# Layer4.net
KiCad netlist of a schematic drawn in EAGLE
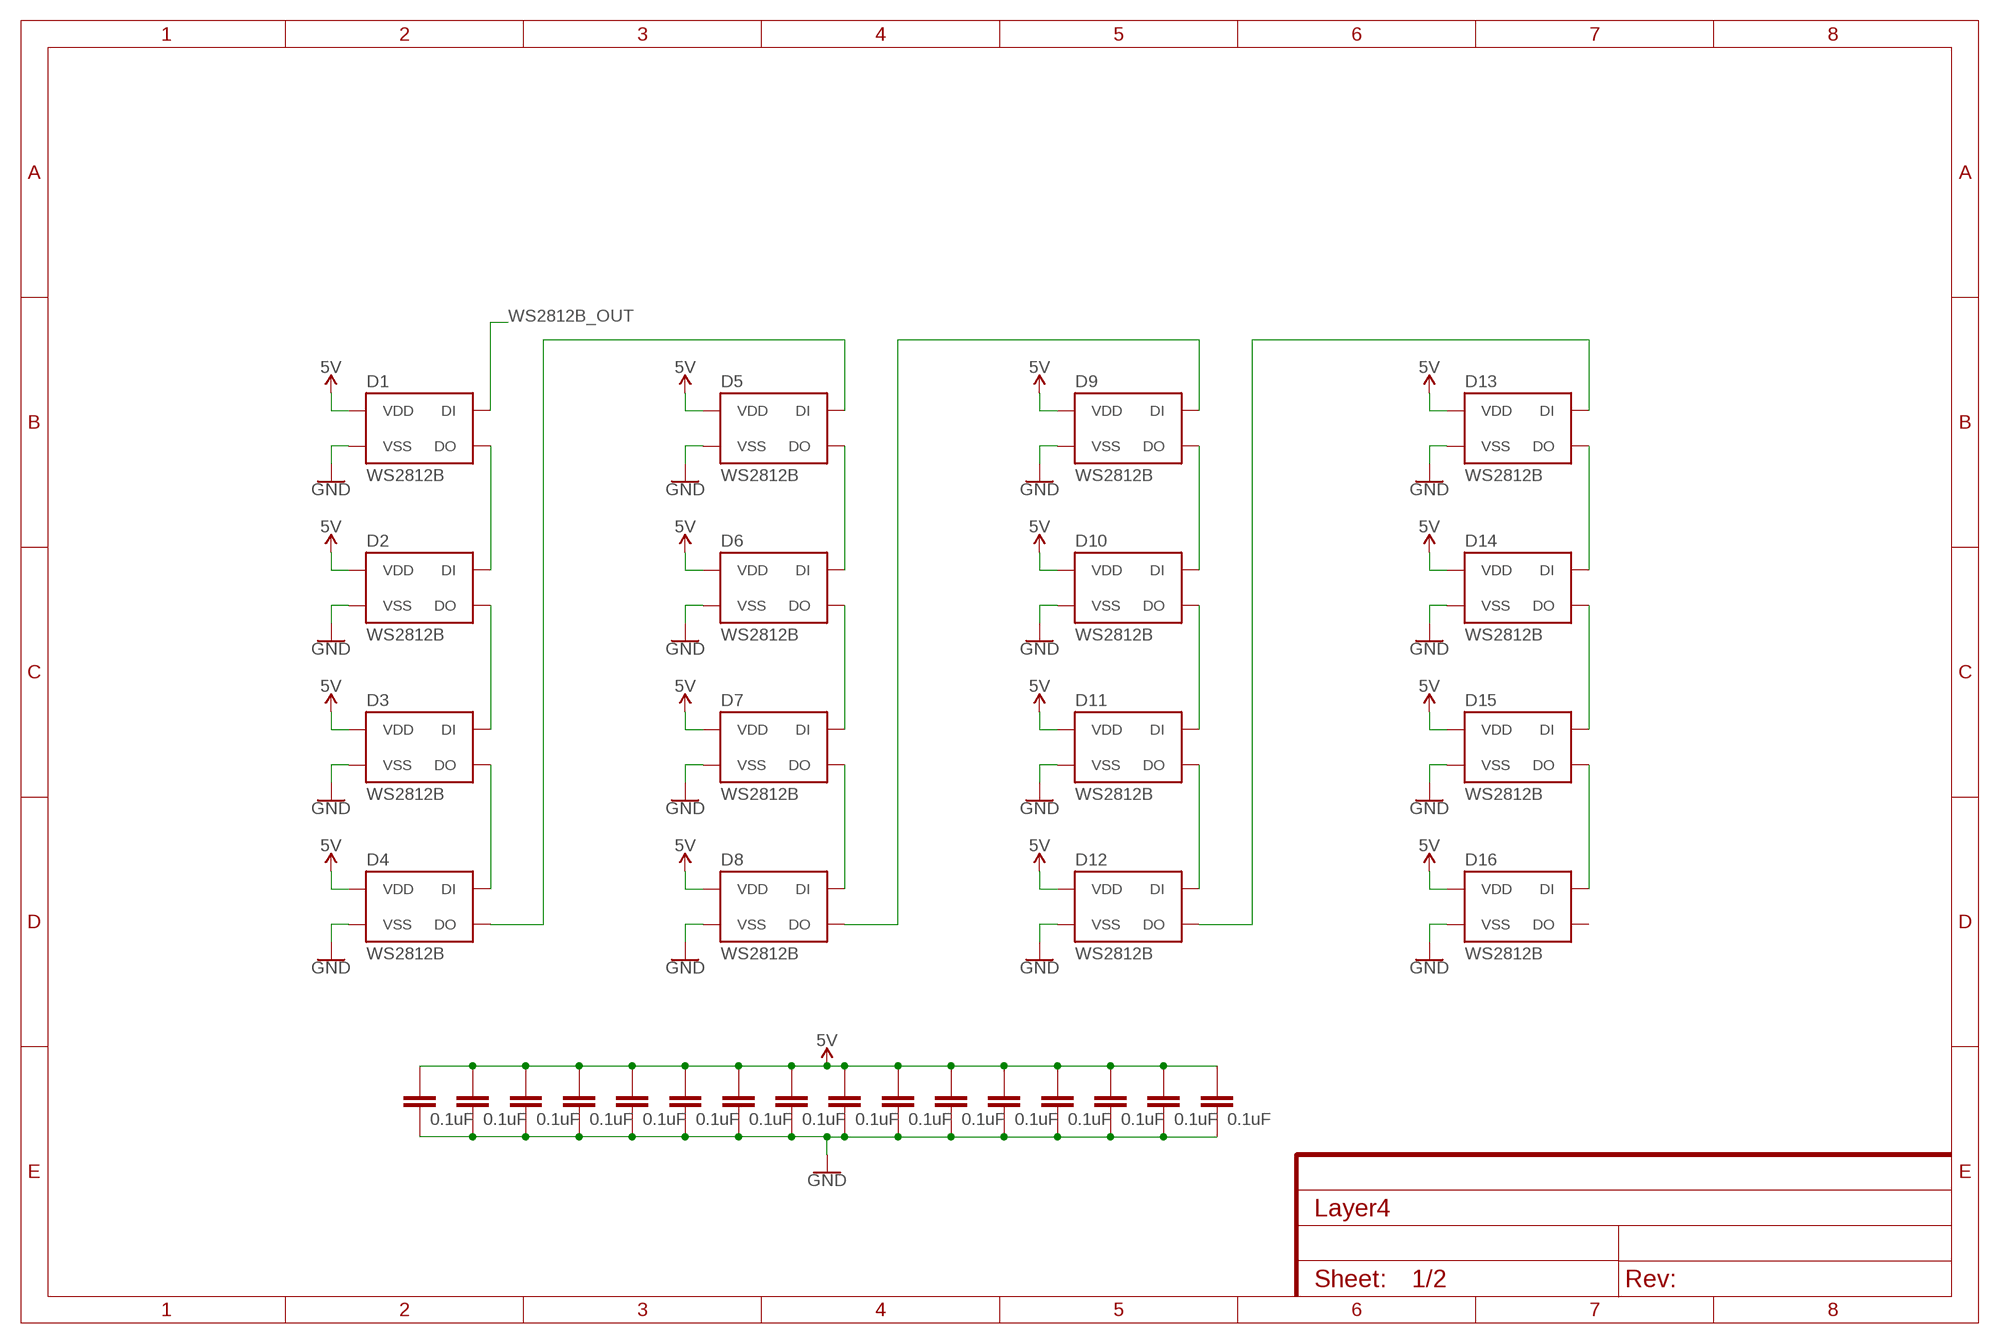
[diagram p0: schematic, sheet 1]
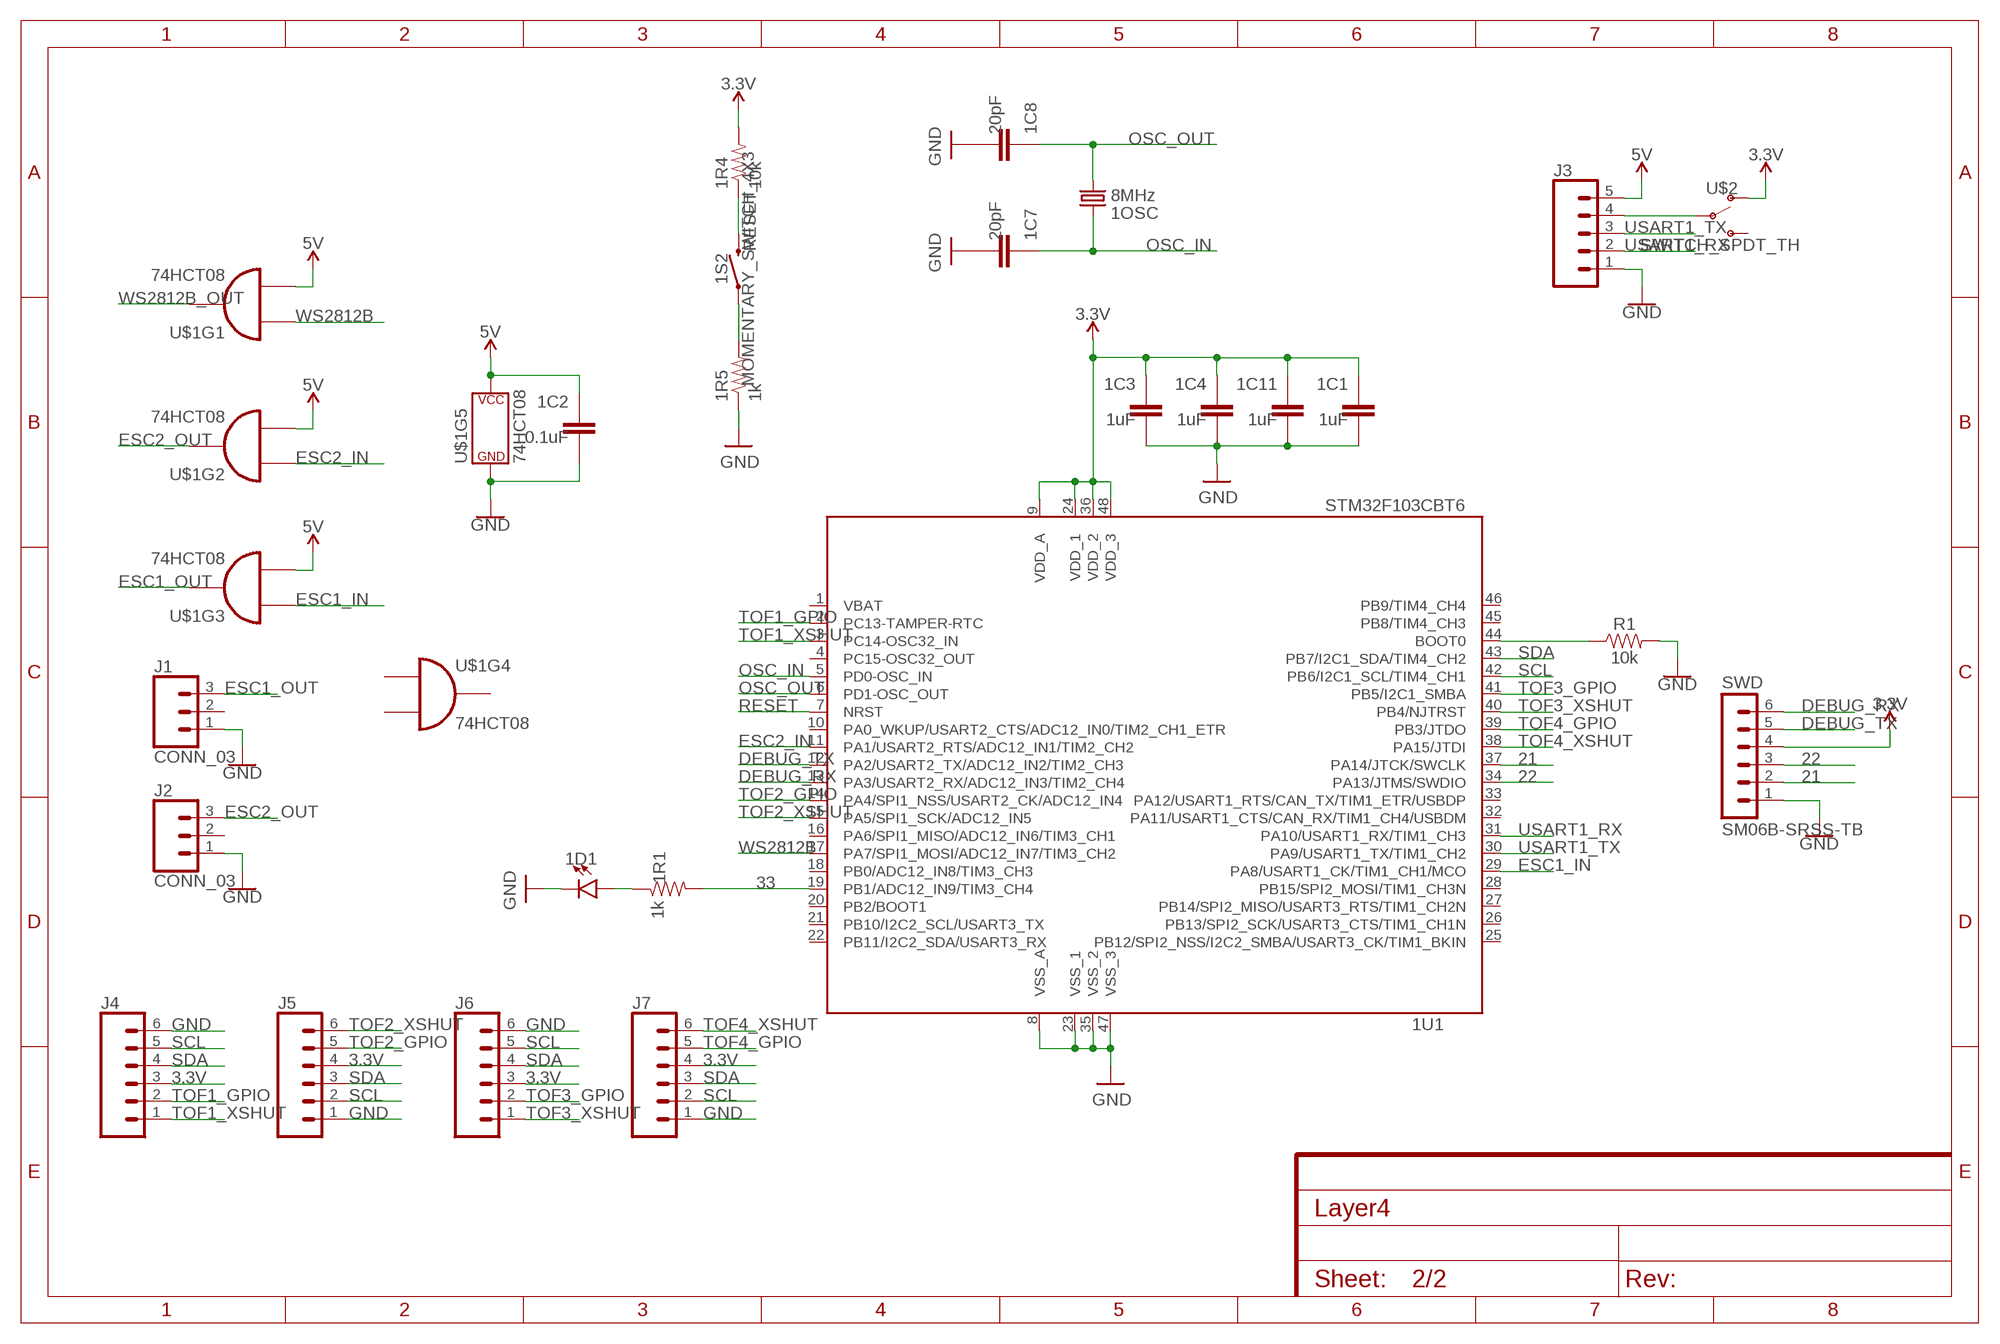
[diagram p1: schematic, sheet 2]

(export (version "E")
  (design (tool "Eeschema 10.0.6"))
  (components
    (comp (ref "AC1")
      (value "0.1uF")
      (footprint "eagle-import:C0603")
      (libsource (lib "eagle-import") (part "CAPACITOR0603"))
    )
    (comp (ref "AC2")
      (value "0.1uF")
      (footprint "eagle-import:C0603")
      (libsource (lib "eagle-import") (part "CAPACITOR0603"))
    )
    (comp (ref "AC3")
      (value "0.1uF")
      (footprint "eagle-import:C0603")
      (libsource (lib "eagle-import") (part "CAPACITOR0603"))
    )
    (comp (ref "AC4")
      (value "0.1uF")
      (footprint "eagle-import:C0603")
      (libsource (lib "eagle-import") (part "CAPACITOR0603"))
    )
    (comp (ref "AC5")
      (value "0.1uF")
      (footprint "eagle-import:C0603")
      (libsource (lib "eagle-import") (part "CAPACITOR0603"))
    )
    (comp (ref "AC6")
      (value "0.1uF")
      (footprint "eagle-import:C0603")
      (libsource (lib "eagle-import") (part "CAPACITOR0603"))
    )
    (comp (ref "AC7")
      (value "0.1uF")
      (footprint "eagle-import:C0603")
      (libsource (lib "eagle-import") (part "CAPACITOR0603"))
    )
    (comp (ref "AC8")
      (value "0.1uF")
      (footprint "eagle-import:C0603")
      (libsource (lib "eagle-import") (part "CAPACITOR0603"))
    )
    (comp (ref "C1")
      (value "0.1uF")
      (footprint "eagle-import:C0603")
      (libsource (lib "eagle-import") (part "CAPACITOR0603"))
    )
    (comp (ref "C3")
      (value "0.1uF")
      (footprint "eagle-import:C0603")
      (libsource (lib "eagle-import") (part "CAPACITOR0603"))
    )
    (comp (ref "C5")
      (value "0.1uF")
      (footprint "eagle-import:C0603")
      (libsource (lib "eagle-import") (part "CAPACITOR0603"))
    )
    (comp (ref "C7")
      (value "0.1uF")
      (footprint "eagle-import:C0603")
      (libsource (lib "eagle-import") (part "CAPACITOR0603"))
    )
    (comp (ref "C9")
      (value "0.1uF")
      (footprint "eagle-import:C0603")
      (libsource (lib "eagle-import") (part "CAPACITOR0603"))
    )
    (comp (ref "C11")
      (value "0.1uF")
      (footprint "eagle-import:C0603")
      (libsource (lib "eagle-import") (part "CAPACITOR0603"))
    )
    (comp (ref "C13")
      (value "0.1uF")
      (footprint "eagle-import:C0603")
      (libsource (lib "eagle-import") (part "CAPACITOR0603"))
    )
    (comp (ref "C15")
      (value "0.1uF")
      (footprint "eagle-import:C0603")
      (libsource (lib "eagle-import") (part "CAPACITOR0603"))
    )
    (comp (ref "D1")
      (value "WS2812B")
      (footprint "eagle-import:WS2812B")
      (libsource (lib "eagle-import") (part "WS2812B"))
    )
    (comp (ref "D2")
      (value "WS2812B")
      (footprint "eagle-import:WS2812B")
      (libsource (lib "eagle-import") (part "WS2812B"))
    )
    (comp (ref "D3")
      (value "WS2812B")
      (footprint "eagle-import:WS2812B")
      (libsource (lib "eagle-import") (part "WS2812B"))
    )
    (comp (ref "D4")
      (value "WS2812B")
      (footprint "eagle-import:WS2812B")
      (libsource (lib "eagle-import") (part "WS2812B"))
    )
    (comp (ref "D5")
      (value "WS2812B")
      (footprint "eagle-import:WS2812B")
      (libsource (lib "eagle-import") (part "WS2812B"))
    )
    (comp (ref "D6")
      (value "WS2812B")
      (footprint "eagle-import:WS2812B")
      (libsource (lib "eagle-import") (part "WS2812B"))
    )
    (comp (ref "D7")
      (value "WS2812B")
      (footprint "eagle-import:WS2812B")
      (libsource (lib "eagle-import") (part "WS2812B"))
    )
    (comp (ref "D8")
      (value "WS2812B")
      (footprint "eagle-import:WS2812B")
      (libsource (lib "eagle-import") (part "WS2812B"))
    )
    (comp (ref "D9")
      (value "WS2812B")
      (footprint "eagle-import:WS2812B")
      (libsource (lib "eagle-import") (part "WS2812B"))
    )
    (comp (ref "D10")
      (value "WS2812B")
      (footprint "eagle-import:WS2812B")
      (libsource (lib "eagle-import") (part "WS2812B"))
    )
    (comp (ref "D11")
      (value "WS2812B")
      (footprint "eagle-import:WS2812B")
      (libsource (lib "eagle-import") (part "WS2812B"))
    )
    (comp (ref "D12")
      (value "WS2812B")
      (footprint "eagle-import:WS2812B")
      (libsource (lib "eagle-import") (part "WS2812B"))
    )
    (comp (ref "D13")
      (value "WS2812B")
      (footprint "eagle-import:WS2812B")
      (libsource (lib "eagle-import") (part "WS2812B"))
    )
    (comp (ref "D14")
      (value "WS2812B")
      (footprint "eagle-import:WS2812B")
      (libsource (lib "eagle-import") (part "WS2812B"))
    )
    (comp (ref "D15")
      (value "WS2812B")
      (footprint "eagle-import:WS2812B")
      (libsource (lib "eagle-import") (part "WS2812B"))
    )
    (comp (ref "D16")
      (value "WS2812B")
      (footprint "eagle-import:WS2812B")
      (libsource (lib "eagle-import") (part "WS2812B"))
    )
    (comp (ref "1C1")
      (value "1uF")
      (footprint "eagle-import:C0603")
      (libsource (lib "eagle-import") (part "CAPACITOR0603"))
    )
    (comp (ref "1C2")
      (value "0.1uF")
      (footprint "eagle-import:C0603")
      (libsource (lib "eagle-import") (part "CAPACITOR0603"))
    )
    (comp (ref "1C3")
      (value "1uF")
      (footprint "eagle-import:C0603")
      (libsource (lib "eagle-import") (part "CAPACITOR0603"))
    )
    (comp (ref "1C4")
      (value "1uF")
      (footprint "eagle-import:C0603")
      (libsource (lib "eagle-import") (part "CAPACITOR0603"))
    )
    (comp (ref "1C7")
      (value "20pF")
      (footprint "eagle-import:C0603")
      (libsource (lib "eagle-import") (part "CAPACITOR0603"))
    )
    (comp (ref "1C8")
      (value "20pF")
      (footprint "eagle-import:C0603")
      (libsource (lib "eagle-import") (part "CAPACITOR0603"))
    )
    (comp (ref "1C11")
      (value "1uF")
      (footprint "eagle-import:C0603")
      (libsource (lib "eagle-import") (part "CAPACITOR0603"))
    )
    (comp (ref "1D1")
      (value "BLUE")
      (footprint "eagle-import:LED-0603")
      (libsource (lib "eagle-import") (part "LED0603"))
    )
    (comp (ref "1OSC")
      (value "8MHz")
      (footprint "eagle-import:CRYSTAL-SMD-5X3.2-2PAD")
      (libsource (lib "eagle-import") (part "CRYSTAL_5032"))
    )
    (comp (ref "1R1")
      (value "1k")
      (footprint "eagle-import:R0603")
      (libsource (lib "eagle-import") (part "RESISTOR0603"))
    )
    (comp (ref "1R4")
      (value "10k")
      (footprint "eagle-import:R0603")
      (libsource (lib "eagle-import") (part "RESISTOR0603"))
    )
    (comp (ref "1R5")
      (value "1k")
      (footprint "eagle-import:R0603")
      (libsource (lib "eagle-import") (part "RESISTOR0603"))
    )
    (comp (ref "1S2")
      (value "MOMENTARY_SWITCH_4X3")
      (footprint "eagle-import:MOMENTARY_SWITCH_4X3")
      (libsource (lib "eagle-import") (part "MOMENTARY_SWITCH_4X3"))
    )
    (comp (ref "1U1")
      (value "STM32F103CBT6")
      (footprint "eagle-import:LQFP48")
      (libsource (lib "eagle-import") (part "STM32F103CBT6"))
    )
    (comp (ref "J1")
      (value "CONN_03")
      (footprint "eagle-import:1X03_LOCK")
      (libsource (lib "eagle-import") (part "CONN_03"))
    )
    (comp (ref "J2")
      (value "CONN_03")
      (footprint "eagle-import:1X03_LOCK")
      (libsource (lib "eagle-import") (part "CONN_03"))
    )
    (comp (ref "J3")
      (value "CONN_05LOCK")
      (footprint "eagle-import:1X05_LOCK")
      (libsource (lib "eagle-import") (part "CONN_05LOCK"))
    )
    (comp (ref "J4")
      (value "CONN_06LOCK")
      (footprint "eagle-import:1X06_LOCK")
      (libsource (lib "eagle-import") (part "CONN_06LOCK"))
    )
    (comp (ref "J5")
      (value "CONN_06LOCK")
      (footprint "eagle-import:1X06_LOCK")
      (libsource (lib "eagle-import") (part "CONN_06LOCK"))
    )
    (comp (ref "J6")
      (value "CONN_06LOCK")
      (footprint "eagle-import:1X06_LOCK")
      (libsource (lib "eagle-import") (part "CONN_06LOCK"))
    )
    (comp (ref "J7")
      (value "CONN_06LOCK")
      (footprint "eagle-import:1X06_LOCK")
      (libsource (lib "eagle-import") (part "CONN_06LOCK"))
    )
    (comp (ref "R1")
      (value "10k")
      (footprint "eagle-import:R0603")
      (libsource (lib "eagle-import") (part "RESISTOR0603"))
    )
    (comp (ref "SWD")
      (value "SM06B-SRSS-TB")
      (footprint "eagle-import:SM06B-SRSS-TB")
      (libsource (lib "eagle-import") (part "SM06B-SRSS-TB"))
    )
    (comp (ref "U$1")
      (value "74HCT08")
      (footprint "eagle-import:SOIC-14")
      (libsource (lib "eagle-import") (part "74HCT08"))
    )
    (comp (ref "U$2")
      (value "SWITCH_SPDT_TH")
      (footprint "eagle-import:SWITCH_SPDT_PTH_11.6X4.0MM_LOCK")
      (libsource (lib "eagle-import") (part "SWITCH_SPDT_TH"))
    )
  )
  (nets
    (net (code "1") (name "3.3V") (class "Default")
      (node (ref "1C1") (pin "1") (pinfunction "1_1") (pintype "passive"))
      (node (ref "1C11") (pin "1") (pinfunction "1_1") (pintype "passive"))
      (node (ref "1C3") (pin "1") (pinfunction "1_1") (pintype "passive"))
      (node (ref "1C4") (pin "1") (pinfunction "1_1") (pintype "passive"))
      (node (ref "1R4") (pin "2") (pinfunction "2_2") (pintype "passive"))
      (node (ref "1U1") (pin "24") (pinfunction "VDD_1_24") (pintype "power_in"))
      (node (ref "1U1") (pin "36") (pinfunction "VDD_2_36") (pintype "power_in"))
      (node (ref "1U1") (pin "48") (pinfunction "VDD_3_48") (pintype "power_in"))
      (node (ref "1U1") (pin "9") (pinfunction "VDD_A_9") (pintype "power_in"))
      (node (ref "J4") (pin "3") (pinfunction "3_3") (pintype "passive"))
      (node (ref "J5") (pin "4") (pinfunction "4_4") (pintype "passive"))
      (node (ref "J6") (pin "3") (pinfunction "3_3") (pintype "passive"))
      (node (ref "J7") (pin "4") (pinfunction "4_4") (pintype "passive"))
      (node (ref "SWD") (pin "4") (pinfunction "4_4") (pintype "passive"))
      (node (ref "U$2") (pin "1") (pinfunction "O_1") (pintype "passive"))
    )
    (net (code "2") (name "5V") (class "Default")
      (node (ref "1C2") (pin "1") (pinfunction "1_1") (pintype "passive"))
      (node (ref "AC1") (pin "1") (pinfunction "1_1") (pintype "passive"))
      (node (ref "AC2") (pin "1") (pinfunction "1_1") (pintype "passive"))
      (node (ref "AC3") (pin "1") (pinfunction "1_1") (pintype "passive"))
      (node (ref "AC4") (pin "1") (pinfunction "1_1") (pintype "passive"))
      (node (ref "AC5") (pin "1") (pinfunction "1_1") (pintype "passive"))
      (node (ref "AC6") (pin "1") (pinfunction "1_1") (pintype "passive"))
      (node (ref "AC7") (pin "1") (pinfunction "1_1") (pintype "passive"))
      (node (ref "AC8") (pin "1") (pinfunction "1_1") (pintype "passive"))
      (node (ref "C1") (pin "1") (pinfunction "1_1") (pintype "passive"))
      (node (ref "C11") (pin "1") (pinfunction "1_1") (pintype "passive"))
      (node (ref "C13") (pin "1") (pinfunction "1_1") (pintype "passive"))
      (node (ref "C15") (pin "1") (pinfunction "1_1") (pintype "passive"))
      (node (ref "C3") (pin "1") (pinfunction "1_1") (pintype "passive"))
      (node (ref "C5") (pin "1") (pinfunction "1_1") (pintype "passive"))
      (node (ref "C7") (pin "1") (pinfunction "1_1") (pintype "passive"))
      (node (ref "C9") (pin "1") (pinfunction "1_1") (pintype "passive"))
      (node (ref "D1") (pin "1") (pinfunction "VDD_1") (pintype "bidirectional"))
      (node (ref "D10") (pin "1") (pinfunction "VDD_1") (pintype "bidirectional"))
      (node (ref "D11") (pin "1") (pinfunction "VDD_1") (pintype "bidirectional"))
      (node (ref "D12") (pin "1") (pinfunction "VDD_1") (pintype "bidirectional"))
      (node (ref "D13") (pin "1") (pinfunction "VDD_1") (pintype "bidirectional"))
      (node (ref "D14") (pin "1") (pinfunction "VDD_1") (pintype "bidirectional"))
      (node (ref "D15") (pin "1") (pinfunction "VDD_1") (pintype "bidirectional"))
      (node (ref "D16") (pin "1") (pinfunction "VDD_1") (pintype "bidirectional"))
      (node (ref "D2") (pin "1") (pinfunction "VDD_1") (pintype "bidirectional"))
      (node (ref "D3") (pin "1") (pinfunction "VDD_1") (pintype "bidirectional"))
      (node (ref "D4") (pin "1") (pinfunction "VDD_1") (pintype "bidirectional"))
      (node (ref "D5") (pin "1") (pinfunction "VDD_1") (pintype "bidirectional"))
      (node (ref "D6") (pin "1") (pinfunction "VDD_1") (pintype "bidirectional"))
      (node (ref "D7") (pin "1") (pinfunction "VDD_1") (pintype "bidirectional"))
      (node (ref "D8") (pin "1") (pinfunction "VDD_1") (pintype "bidirectional"))
      (node (ref "D9") (pin "1") (pinfunction "VDD_1") (pintype "bidirectional"))
      (node (ref "J3") (pin "5") (pinfunction "5_5") (pintype "passive"))
      (node (ref "U$1") (pin "P10") (pinfunction "I1_P10") (pintype "input"))
      (node (ref "U$1") (pin "P14") (pinfunction "P$V+_P14") (pintype "bidirectional"))
      (node (ref "U$1") (pin "P2") (pinfunction "I1_P2") (pintype "input"))
      (node (ref "U$1") (pin "P5") (pinfunction "I1_P5") (pintype "input"))
    )
    (net (code "3") (name "21") (class "Default")
      (node (ref "1U1") (pin "37") (pinfunction "PA14/JTCK/SWCLK_37") (pintype "bidirectional"))
      (node (ref "SWD") (pin "2") (pinfunction "2_2") (pintype "passive"))
    )
    (net (code "4") (name "22") (class "Default")
      (node (ref "1U1") (pin "34") (pinfunction "PA13/JTMS/SWDIO_34") (pintype "bidirectional"))
      (node (ref "SWD") (pin "3") (pinfunction "3_3") (pintype "passive"))
    )
    (net (code "5") (name "33") (class "Default")
      (node (ref "1R1") (pin "2") (pinfunction "2_2") (pintype "passive"))
      (node (ref "1U1") (pin "19") (pinfunction "PB1/ADC12_IN9/TIM3_CH4_19") (pintype "bidirectional"))
    )
    (net (code "6") (name "DEBUG_RX") (class "Default")
      (node (ref "1U1") (pin "13") (pinfunction "PA3/USART2_RX/ADC12_IN3/TIM2_CH4_13") (pintype "bidirectional"))
      (node (ref "SWD") (pin "6") (pinfunction "6_6") (pintype "passive"))
    )
    (net (code "7") (name "DEBUG_TX") (class "Default")
      (node (ref "1U1") (pin "12") (pinfunction "PA2/USART2_TX/ADC12_IN2/TIM2_CH3_12") (pintype "bidirectional"))
      (node (ref "SWD") (pin "5") (pinfunction "5_5") (pintype "passive"))
    )
    (net (code "8") (name "ESC1_IN") (class "Default")
      (node (ref "1U1") (pin "29") (pinfunction "PA8/USART1_CK/TIM1_CH1/MCO_29") (pintype "bidirectional"))
      (node (ref "U$1") (pin "P9") (pinfunction "I0_P9") (pintype "input"))
    )
    (net (code "9") (name "ESC1_OUT") (class "Default")
      (node (ref "J1") (pin "3") (pinfunction "3_3") (pintype "passive"))
      (node (ref "U$1") (pin "P8") (pinfunction "O_P8") (pintype "output"))
    )
    (net (code "10") (name "ESC2_IN") (class "Default")
      (node (ref "1U1") (pin "11") (pinfunction "PA1/USART2_RTS/ADC12_IN1/TIM2_CH2_11") (pintype "bidirectional"))
      (node (ref "U$1") (pin "P4") (pinfunction "I0_P4") (pintype "input"))
    )
    (net (code "11") (name "ESC2_OUT") (class "Default")
      (node (ref "J2") (pin "3") (pinfunction "3_3") (pintype "passive"))
      (node (ref "U$1") (pin "P6") (pinfunction "O_P6") (pintype "output"))
    )
    (net (code "12") (name "GND") (class "Default")
      (node (ref "1C1") (pin "2") (pinfunction "2_2") (pintype "passive"))
      (node (ref "1C11") (pin "2") (pinfunction "2_2") (pintype "passive"))
      (node (ref "1C2") (pin "2") (pinfunction "2_2") (pintype "passive"))
      (node (ref "1C3") (pin "2") (pinfunction "2_2") (pintype "passive"))
      (node (ref "1C4") (pin "2") (pinfunction "2_2") (pintype "passive"))
      (node (ref "1C7") (pin "2") (pinfunction "2_2") (pintype "passive"))
      (node (ref "1C8") (pin "2") (pinfunction "2_2") (pintype "passive"))
      (node (ref "1D1") (pin "C") (pinfunction "C_C") (pintype "passive"))
      (node (ref "1R5") (pin "1") (pinfunction "1_1") (pintype "passive"))
      (node (ref "1U1") (pin "23") (pinfunction "VSS_1_23") (pintype "power_in"))
      (node (ref "1U1") (pin "35") (pinfunction "VSS_2_35") (pintype "power_in"))
      (node (ref "1U1") (pin "47") (pinfunction "VSS_3_47") (pintype "power_in"))
      (node (ref "1U1") (pin "8") (pinfunction "VSS_A_8") (pintype "power_in"))
      (node (ref "AC1") (pin "2") (pinfunction "2_2") (pintype "passive"))
      (node (ref "AC2") (pin "2") (pinfunction "2_2") (pintype "passive"))
      (node (ref "AC3") (pin "2") (pinfunction "2_2") (pintype "passive"))
      (node (ref "AC4") (pin "2") (pinfunction "2_2") (pintype "passive"))
      (node (ref "AC5") (pin "2") (pinfunction "2_2") (pintype "passive"))
      (node (ref "AC6") (pin "2") (pinfunction "2_2") (pintype "passive"))
      (node (ref "AC7") (pin "2") (pinfunction "2_2") (pintype "passive"))
      (node (ref "AC8") (pin "2") (pinfunction "2_2") (pintype "passive"))
      (node (ref "C1") (pin "2") (pinfunction "2_2") (pintype "passive"))
      (node (ref "C11") (pin "2") (pinfunction "2_2") (pintype "passive"))
      (node (ref "C13") (pin "2") (pinfunction "2_2") (pintype "passive"))
      (node (ref "C15") (pin "2") (pinfunction "2_2") (pintype "passive"))
      (node (ref "C3") (pin "2") (pinfunction "2_2") (pintype "passive"))
      (node (ref "C5") (pin "2") (pinfunction "2_2") (pintype "passive"))
      (node (ref "C7") (pin "2") (pinfunction "2_2") (pintype "passive"))
      (node (ref "C9") (pin "2") (pinfunction "2_2") (pintype "passive"))
      (node (ref "D1") (pin "3") (pinfunction "VSS_3") (pintype "bidirectional"))
      (node (ref "D10") (pin "3") (pinfunction "VSS_3") (pintype "bidirectional"))
      (node (ref "D11") (pin "3") (pinfunction "VSS_3") (pintype "bidirectional"))
      (node (ref "D12") (pin "3") (pinfunction "VSS_3") (pintype "bidirectional"))
      (node (ref "D13") (pin "3") (pinfunction "VSS_3") (pintype "bidirectional"))
      (node (ref "D14") (pin "3") (pinfunction "VSS_3") (pintype "bidirectional"))
      (node (ref "D15") (pin "3") (pinfunction "VSS_3") (pintype "bidirectional"))
      (node (ref "D16") (pin "3") (pinfunction "VSS_3") (pintype "bidirectional"))
      (node (ref "D2") (pin "3") (pinfunction "VSS_3") (pintype "bidirectional"))
      (node (ref "D3") (pin "3") (pinfunction "VSS_3") (pintype "bidirectional"))
      (node (ref "D4") (pin "3") (pinfunction "VSS_3") (pintype "bidirectional"))
      (node (ref "D5") (pin "3") (pinfunction "VSS_3") (pintype "bidirectional"))
      (node (ref "D6") (pin "3") (pinfunction "VSS_3") (pintype "bidirectional"))
      (node (ref "D7") (pin "3") (pinfunction "VSS_3") (pintype "bidirectional"))
      (node (ref "D8") (pin "3") (pinfunction "VSS_3") (pintype "bidirectional"))
      (node (ref "D9") (pin "3") (pinfunction "VSS_3") (pintype "bidirectional"))
      (node (ref "J1") (pin "1") (pinfunction "1_1") (pintype "passive"))
      (node (ref "J2") (pin "1") (pinfunction "1_1") (pintype "passive"))
      (node (ref "J3") (pin "1") (pinfunction "1_1") (pintype "passive"))
      (node (ref "J4") (pin "6") (pinfunction "6_6") (pintype "passive"))
      (node (ref "J5") (pin "1") (pinfunction "1_1") (pintype "passive"))
      (node (ref "J6") (pin "6") (pinfunction "6_6") (pintype "passive"))
      (node (ref "J7") (pin "1") (pinfunction "1_1") (pintype "passive"))
      (node (ref "R1") (pin "2") (pinfunction "2_2") (pintype "passive"))
      (node (ref "SWD") (pin "1") (pinfunction "1_1") (pintype "passive"))
      (node (ref "U$1") (pin "P7") (pinfunction "P$V-_P7") (pintype "bidirectional"))
    )
    (net (code "13") (name "Net-(1D1-PadA)") (class "Default")
      (node (ref "1D1") (pin "A") (pinfunction "A_A") (pintype "passive"))
      (node (ref "1R1") (pin "1") (pinfunction "1_1") (pintype "passive"))
    )
    (net (code "14") (name "Net-(1S2-1)") (class "Default")
      (node (ref "1R5") (pin "2") (pinfunction "2_2") (pintype "passive"))
      (node (ref "1S2") (pin "P$1") (pinfunction "1_P$1") (pintype "passive"))
    )
    (net (code "15") (name "Net-(1U1-BOOT0)") (class "Default")
      (node (ref "1U1") (pin "44") (pinfunction "BOOT0_44") (pintype "input"))
      (node (ref "R1") (pin "1") (pinfunction "1_1") (pintype "passive"))
    )
    (net (code "16") (name "Net-(D1-DO)") (class "Default")
      (node (ref "D1") (pin "2") (pinfunction "DO_2") (pintype "bidirectional"))
      (node (ref "D2") (pin "4") (pinfunction "DI_4") (pintype "bidirectional"))
    )
    (net (code "17") (name "Net-(D2-DO)") (class "Default")
      (node (ref "D2") (pin "2") (pinfunction "DO_2") (pintype "bidirectional"))
      (node (ref "D3") (pin "4") (pinfunction "DI_4") (pintype "bidirectional"))
    )
    (net (code "18") (name "Net-(D3-DO)") (class "Default")
      (node (ref "D3") (pin "2") (pinfunction "DO_2") (pintype "bidirectional"))
      (node (ref "D4") (pin "4") (pinfunction "DI_4") (pintype "bidirectional"))
    )
    (net (code "19") (name "Net-(D4-DO)") (class "Default")
      (node (ref "D4") (pin "2") (pinfunction "DO_2") (pintype "bidirectional"))
      (node (ref "D5") (pin "4") (pinfunction "DI_4") (pintype "bidirectional"))
    )
    (net (code "20") (name "Net-(D5-DO)") (class "Default")
      (node (ref "D5") (pin "2") (pinfunction "DO_2") (pintype "bidirectional"))
      (node (ref "D6") (pin "4") (pinfunction "DI_4") (pintype "bidirectional"))
    )
    (net (code "21") (name "Net-(D6-DO)") (class "Default")
      (node (ref "D6") (pin "2") (pinfunction "DO_2") (pintype "bidirectional"))
      (node (ref "D7") (pin "4") (pinfunction "DI_4") (pintype "bidirectional"))
    )
    (net (code "22") (name "Net-(D7-DO)") (class "Default")
      (node (ref "D7") (pin "2") (pinfunction "DO_2") (pintype "bidirectional"))
      (node (ref "D8") (pin "4") (pinfunction "DI_4") (pintype "bidirectional"))
    )
    (net (code "23") (name "Net-(D8-DO)") (class "Default")
      (node (ref "D8") (pin "2") (pinfunction "DO_2") (pintype "bidirectional"))
      (node (ref "D9") (pin "4") (pinfunction "DI_4") (pintype "bidirectional"))
    )
    (net (code "24") (name "Net-(D10-DI)") (class "Default")
      (node (ref "D10") (pin "4") (pinfunction "DI_4") (pintype "bidirectional"))
      (node (ref "D9") (pin "2") (pinfunction "DO_2") (pintype "bidirectional"))
    )
    (net (code "25") (name "Net-(D10-DO)") (class "Default")
      (node (ref "D10") (pin "2") (pinfunction "DO_2") (pintype "bidirectional"))
      (node (ref "D11") (pin "4") (pinfunction "DI_4") (pintype "bidirectional"))
    )
    (net (code "26") (name "Net-(D11-DO)") (class "Default")
      (node (ref "D11") (pin "2") (pinfunction "DO_2") (pintype "bidirectional"))
      (node (ref "D12") (pin "4") (pinfunction "DI_4") (pintype "bidirectional"))
    )
    (net (code "27") (name "Net-(D12-DO)") (class "Default")
      (node (ref "D12") (pin "2") (pinfunction "DO_2") (pintype "bidirectional"))
      (node (ref "D13") (pin "4") (pinfunction "DI_4") (pintype "bidirectional"))
    )
    (net (code "28") (name "Net-(D13-DO)") (class "Default")
      (node (ref "D13") (pin "2") (pinfunction "DO_2") (pintype "bidirectional"))
      (node (ref "D14") (pin "4") (pinfunction "DI_4") (pintype "bidirectional"))
    )
    (net (code "29") (name "Net-(D14-DO)") (class "Default")
      (node (ref "D14") (pin "2") (pinfunction "DO_2") (pintype "bidirectional"))
      (node (ref "D15") (pin "4") (pinfunction "DI_4") (pintype "bidirectional"))
    )
    (net (code "30") (name "Net-(D15-DO)") (class "Default")
      (node (ref "D15") (pin "2") (pinfunction "DO_2") (pintype "bidirectional"))
      (node (ref "D16") (pin "4") (pinfunction "DI_4") (pintype "bidirectional"))
    )
    (net (code "31") (name "Net-(U$2-P)") (class "Default")
      (node (ref "J3") (pin "4") (pinfunction "4_4") (pintype "passive"))
      (node (ref "U$2") (pin "2") (pinfunction "P_2") (pintype "passive"))
    )
    (net (code "32") (name "OSC_IN") (class "Default")
      (node (ref "1C7") (pin "1") (pinfunction "1_1") (pintype "passive"))
      (node (ref "1OSC") (pin "P$2") (pinfunction "2_P$2") (pintype "passive"))
      (node (ref "1U1") (pin "5") (pinfunction "PD0-OSC_IN_5") (pintype "input"))
    )
    (net (code "33") (name "OSC_OUT") (class "Default")
      (node (ref "1C8") (pin "1") (pinfunction "1_1") (pintype "passive"))
      (node (ref "1OSC") (pin "P$1") (pinfunction "1_P$1") (pintype "passive"))
      (node (ref "1U1") (pin "6") (pinfunction "PD1-OSC_OUT_6") (pintype "input"))
    )
    (net (code "34") (name "RESET") (class "Default")
      (node (ref "1R4") (pin "1") (pinfunction "1_1") (pintype "passive"))
      (node (ref "1S2") (pin "P$2") (pinfunction "2_P$2") (pintype "passive"))
      (node (ref "1U1") (pin "7") (pinfunction "NRST_7") (pintype "input"))
    )
    (net (code "35") (name "SCL") (class "Default")
      (node (ref "1U1") (pin "42") (pinfunction "PB6/I2C1_SCL/TIM4_CH1_42") (pintype "input"))
      (node (ref "J4") (pin "5") (pinfunction "5_5") (pintype "passive"))
      (node (ref "J5") (pin "2") (pinfunction "2_2") (pintype "passive"))
      (node (ref "J6") (pin "5") (pinfunction "5_5") (pintype "passive"))
      (node (ref "J7") (pin "2") (pinfunction "2_2") (pintype "passive"))
    )
    (net (code "36") (name "SDA") (class "Default")
      (node (ref "1U1") (pin "43") (pinfunction "PB7/I2C1_SDA/TIM4_CH2_43") (pintype "bidirectional"))
      (node (ref "J4") (pin "4") (pinfunction "4_4") (pintype "passive"))
      (node (ref "J5") (pin "3") (pinfunction "3_3") (pintype "passive"))
      (node (ref "J6") (pin "4") (pinfunction "4_4") (pintype "passive"))
      (node (ref "J7") (pin "3") (pinfunction "3_3") (pintype "passive"))
    )
    (net (code "37") (name "TOF1_GPIO") (class "Default")
      (node (ref "1U1") (pin "2") (pinfunction "PC13-TAMPER-RTC_2") (pintype "input"))
      (node (ref "J4") (pin "2") (pinfunction "2_2") (pintype "passive"))
    )
    (net (code "38") (name "TOF1_XSHUT") (class "Default")
      (node (ref "1U1") (pin "3") (pinfunction "PC14-OSC32_IN_3") (pintype "input"))
      (node (ref "J4") (pin "1") (pinfunction "1_1") (pintype "passive"))
    )
    (net (code "39") (name "TOF2_GPIO") (class "Default")
      (node (ref "1U1") (pin "14") (pinfunction "PA4/SPI1_NSS/USART2_CK/ADC12_IN4_14") (pintype "bidirectional"))
      (node (ref "J5") (pin "5") (pinfunction "5_5") (pintype "passive"))
    )
    (net (code "40") (name "TOF2_XSHUT") (class "Default")
      (node (ref "1U1") (pin "15") (pinfunction "PA5/SPI1_SCK/ADC12_IN5_15") (pintype "bidirectional"))
      (node (ref "J5") (pin "6") (pinfunction "6_6") (pintype "passive"))
    )
    (net (code "41") (name "TOF3_GPIO") (class "Default")
      (node (ref "1U1") (pin "41") (pinfunction "PB5/I2C1_SMBA_41") (pintype "input"))
      (node (ref "J6") (pin "2") (pinfunction "2_2") (pintype "passive"))
    )
    (net (code "42") (name "TOF3_XSHUT") (class "Default")
      (node (ref "1U1") (pin "40") (pinfunction "PB4/NJTRST_40") (pintype "bidirectional"))
      (node (ref "J6") (pin "1") (pinfunction "1_1") (pintype "passive"))
    )
    (net (code "43") (name "TOF4_GPIO") (class "Default")
      (node (ref "1U1") (pin "39") (pinfunction "PB3/JTDO_39") (pintype "bidirectional"))
      (node (ref "J7") (pin "5") (pinfunction "5_5") (pintype "passive"))
    )
    (net (code "44") (name "TOF4_XSHUT") (class "Default")
      (node (ref "1U1") (pin "38") (pinfunction "PA15/JTDI_38") (pintype "bidirectional"))
      (node (ref "J7") (pin "6") (pinfunction "6_6") (pintype "passive"))
    )
    (net (code "45") (name "USART1_RX") (class "Default")
      (node (ref "1U1") (pin "31") (pinfunction "PA10/USART1_RX/TIM1_CH3_31") (pintype "bidirectional"))
      (node (ref "J3") (pin "2") (pinfunction "2_2") (pintype "passive"))
    )
    (net (code "46") (name "USART1_TX") (class "Default")
      (node (ref "1U1") (pin "30") (pinfunction "PA9/USART1_TX/TIM1_CH2_30") (pintype "input"))
      (node (ref "J3") (pin "3") (pinfunction "3_3") (pintype "passive"))
    )
    (net (code "47") (name "VBAT") (class "Default")
      (node (ref "1U1") (pin "1") (pinfunction "VBAT_1") (pintype "power_in"))
    )
    (net (code "48") (name "WS2812B") (class "Default")
      (node (ref "1U1") (pin "17") (pinfunction "PA7/SPI1_MOSI/ADC12_IN7/TIM3_CH2_17") (pintype "bidirectional"))
      (node (ref "U$1") (pin "P1") (pinfunction "I0_P1") (pintype "input"))
    )
    (net (code "49") (name "WS2812B_OUT") (class "Default")
      (node (ref "D1") (pin "4") (pinfunction "DI_4") (pintype "bidirectional"))
      (node (ref "U$1") (pin "P3") (pinfunction "O_P3") (pintype "output"))
    )
    (net (code "50") (name "unconnected-(1U1-PA0_WKUP{slash}USART2_CTS{slash}ADC12_IN0{slash}TIM2_CH1_ETR-Pad10)") (class "Default")
      (node (ref "1U1") (pin "10") (pinfunction "PA0_WKUP/USART2_CTS/ADC12_IN0/TIM2_CH1_ETR_10") (pintype "bidirectional"))
    )
    (net (code "51") (name "unconnected-(1U1-PA6{slash}SPI1_MISO{slash}ADC12_IN6{slash}TIM3_CH1-Pad16)") (class "Default")
      (node (ref "1U1") (pin "16") (pinfunction "PA6/SPI1_MISO/ADC12_IN6/TIM3_CH1_16") (pintype "bidirectional"))
    )
    (net (code "52") (name "unconnected-(1U1-PA11{slash}USART1_CTS{slash}CAN_RX{slash}TIM1_CH4{slash}USBDM-Pad32)") (class "Default")
      (node (ref "1U1") (pin "32") (pinfunction "PA11/USART1_CTS/CAN_RX/TIM1_CH4/USBDM_32") (pintype "bidirectional"))
    )
    (net (code "53") (name "unconnected-(1U1-PA12{slash}USART1_RTS{slash}CAN_TX{slash}TIM1_ETR{slash}USBDP-Pad33)") (class "Default")
      (node (ref "1U1") (pin "33") (pinfunction "PA12/USART1_RTS/CAN_TX/TIM1_ETR/USBDP_33") (pintype "bidirectional"))
    )
    (net (code "54") (name "unconnected-(1U1-PB0{slash}ADC12_IN8{slash}TIM3_CH3-Pad18)") (class "Default")
      (node (ref "1U1") (pin "18") (pinfunction "PB0/ADC12_IN8/TIM3_CH3_18") (pintype "bidirectional"))
    )
    (net (code "55") (name "unconnected-(1U1-PB2{slash}BOOT1-Pad20)") (class "Default")
      (node (ref "1U1") (pin "20") (pinfunction "PB2/BOOT1_20") (pintype "bidirectional"))
    )
    (net (code "56") (name "unconnected-(1U1-PB8{slash}TIM4_CH3-Pad45)") (class "Default")
      (node (ref "1U1") (pin "45") (pinfunction "PB8/TIM4_CH3_45") (pintype "bidirectional"))
    )
    (net (code "57") (name "unconnected-(1U1-PB9{slash}TIM4_CH4-Pad46)") (class "Default")
      (node (ref "1U1") (pin "46") (pinfunction "PB9/TIM4_CH4_46") (pintype "input"))
    )
    (net (code "58") (name "unconnected-(1U1-PB10{slash}I2C2_SCL{slash}USART3_TX-Pad21)") (class "Default")
      (node (ref "1U1") (pin "21") (pinfunction "PB10/I2C2_SCL/USART3_TX_21") (pintype "input"))
    )
    (net (code "59") (name "unconnected-(1U1-PB11{slash}I2C2_SDA{slash}USART3_RX-Pad22)") (class "Default")
      (node (ref "1U1") (pin "22") (pinfunction "PB11/I2C2_SDA/USART3_RX_22") (pintype "input"))
    )
    (net (code "60") (name "unconnected-(1U1-PB12{slash}SPI2_NSS{slash}I2C2_SMBA{slash}USART3_CK{slash}TIM1_BKIN-Pad25)") (class "Default")
      (node (ref "1U1") (pin "25") (pinfunction "PB12/SPI2_NSS/I2C2_SMBA/USART3_CK/TIM1_BKIN_25") (pintype "input"))
    )
    (net (code "61") (name "unconnected-(1U1-PB13{slash}SPI2_SCK{slash}USART3_CTS{slash}TIM1_CH1N-Pad26)") (class "Default")
      (node (ref "1U1") (pin "26") (pinfunction "PB13/SPI2_SCK/USART3_CTS/TIM1_CH1N_26") (pintype "input"))
    )
    (net (code "62") (name "unconnected-(1U1-PB14{slash}SPI2_MISO{slash}USART3_RTS{slash}TIM1_CH2N-Pad27)") (class "Default")
      (node (ref "1U1") (pin "27") (pinfunction "PB14/SPI2_MISO/USART3_RTS/TIM1_CH2N_27") (pintype "input"))
    )
    (net (code "63") (name "unconnected-(1U1-PB15{slash}SPI2_MOSI{slash}TIM1_CH3N-Pad28)") (class "Default")
      (node (ref "1U1") (pin "28") (pinfunction "PB15/SPI2_MOSI/TIM1_CH3N_28") (pintype "input"))
    )
    (net (code "64") (name "unconnected-(1U1-PC15-OSC32_OUT-Pad4)") (class "Default")
      (node (ref "1U1") (pin "4") (pinfunction "PC15-OSC32_OUT_4") (pintype "input"))
    )
    (net (code "65") (name "unconnected-(D16-DO-Pad2)") (class "Default")
      (node (ref "D16") (pin "2") (pinfunction "DO_2") (pintype "bidirectional"))
    )
    (net (code "66") (name "unconnected-(J1-Pad2)") (class "Default")
      (node (ref "J1") (pin "2") (pinfunction "2_2") (pintype "passive"))
    )
    (net (code "67") (name "unconnected-(J2-Pad2)") (class "Default")
      (node (ref "J2") (pin "2") (pinfunction "2_2") (pintype "passive"))
    )
    (net (code "68") (name "unconnected-(U$1D-I0-PadP12)") (class "Default")
      (node (ref "U$1") (pin "P12") (pinfunction "I0_P12") (pintype "input"))
    )
    (net (code "69") (name "unconnected-(U$1D-I1-PadP13)") (class "Default")
      (node (ref "U$1") (pin "P13") (pinfunction "I1_P13") (pintype "input"))
    )
    (net (code "70") (name "unconnected-(U$1D-O-PadP11)") (class "Default")
      (node (ref "U$1") (pin "P11") (pinfunction "O_P11") (pintype "output"))
    )
    (net (code "71") (name "unconnected-(U$2-S-Pad3)") (class "Default")
      (node (ref "U$2") (pin "3") (pinfunction "S_3") (pintype "passive"))
    )
  )
)
